# An_lisis_punto_DC.net
KiCad netlist of a schematic drawn in Altium Designer
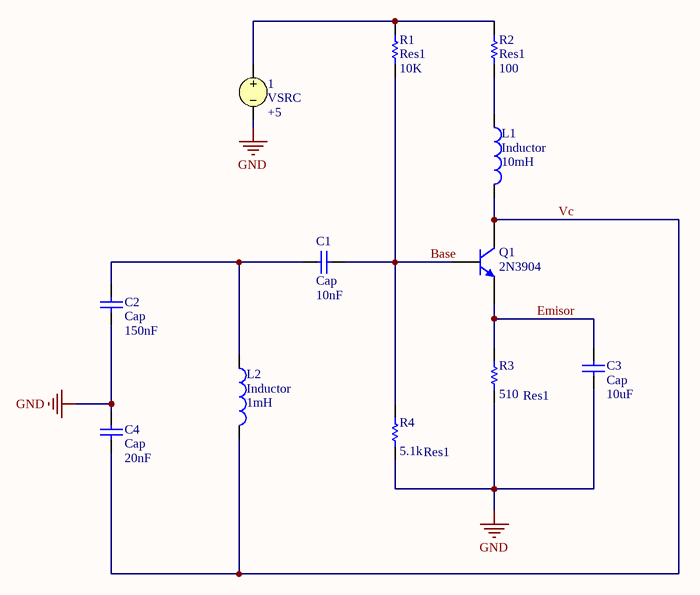
[diagram p0: Análisis_punto_DC.SchDoc]

(export (version "E")
  (design (tool "Eeschema 10.0.6"))
  (components
    (comp (ref "1")
      (value "VSRC")
      (description "Voltage Source")
      (fields (field (name "ALTIUM_VALUE") "+5") (field (name "PUBLISHER") "Altium Limited"))
      (libsource (lib "Simulation Sources") (part "VSRC"))
    )
    (comp (ref "C1")
      (value "Cap")
      (footprint "RAD-0.3")
      (description "Capacitor")
      (fields (field (name "ALTIUM_VALUE") "10nF") (field (name "PUBLISHER") "Altium Limited"))
      (libsource (lib "Miscellaneous Devices") (part "Cap"))
    )
    (comp (ref "C2")
      (value "Cap")
      (footprint "RAD-0.3")
      (description "Capacitor")
      (fields (field (name "ALTIUM_VALUE") "150nF") (field (name "PUBLISHER") "Altium Limited"))
      (libsource (lib "Miscellaneous Devices") (part "Cap"))
    )
    (comp (ref "C3")
      (value "Cap")
      (footprint "RAD-0.3")
      (description "Capacitor")
      (fields (field (name "ALTIUM_VALUE") "10uF") (field (name "PUBLISHER") "Altium Limited"))
      (libsource (lib "Miscellaneous Devices") (part "Cap"))
    )
    (comp (ref "C4")
      (value "Cap")
      (footprint "RAD-0.3")
      (description "Capacitor")
      (fields (field (name "ALTIUM_VALUE") "20nF") (field (name "PUBLISHER") "Altium Limited"))
      (libsource (lib "Miscellaneous Devices") (part "Cap"))
    )
    (comp (ref "L1")
      (value "Inductor")
      (footprint "0402-A")
      (fields (field (name "ALTIUM_VALUE") "10mH") (field (name "PUBLISHER") "Altium Limited"))
      (libsource (lib "Miscellaneous Devices") (part "Inductor"))
    )
    (comp (ref "L2")
      (value "Inductor")
      (footprint "0402-A")
      (fields (field (name "ALTIUM_VALUE") "1mH") (field (name "PUBLISHER") "Altium Limited"))
      (libsource (lib "Miscellaneous Devices") (part "Inductor"))
    )
    (comp (ref "Q1")
      (value "2N3904")
      (footprint "TO-92A")
      (description "NPN General Purpose Amplifier")
      (fields (field (name "PUBLISHER") "Altium Limited"))
      (libsource (lib "Miscellaneous Devices") (part "2N3904"))
    )
    (comp (ref "R1")
      (value "Res1")
      (footprint "AXIAL-0.3")
      (description "Resistor")
      (fields (field (name "ALTIUM_VALUE") "10K") (field (name "PUBLISHER") "Altium Limited"))
      (libsource (lib "Miscellaneous Devices") (part "Res1"))
    )
    (comp (ref "R2")
      (value "Res1")
      (footprint "AXIAL-0.3")
      (description "Resistor")
      (fields (field (name "ALTIUM_VALUE") "100") (field (name "PUBLISHER") "Altium Limited"))
      (libsource (lib "Miscellaneous Devices") (part "Res1"))
    )
    (comp (ref "R3")
      (value "Res1")
      (footprint "AXIAL-0.3")
      (description "Resistor")
      (fields (field (name "ALTIUM_VALUE") "510") (field (name "PUBLISHER") "Altium Limited"))
      (libsource (lib "Miscellaneous Devices") (part "Res1"))
    )
    (comp (ref "R4")
      (value "Res1")
      (footprint "AXIAL-0.3")
      (description "Resistor")
      (fields (field (name "ALTIUM_VALUE") "5.1k") (field (name "PUBLISHER") "Altium Limited"))
      (libsource (lib "Miscellaneous Devices") (part "Res1"))
    )
  )
  (nets
    (net (code "1") (name "/Base") (class "Default")
      (node (ref "C1") (pin "1") (pinfunction "1_1") (pintype "passive"))
      (node (ref "Q1") (pin "2") (pinfunction "B_2") (pintype "passive"))
      (node (ref "R1") (pin "1") (pinfunction "1_1") (pintype "passive"))
      (node (ref "R4") (pin "2") (pinfunction "2_2") (pintype "passive"))
    )
    (net (code "2") (name "/Emisor") (class "Default")
      (node (ref "C3") (pin "2") (pinfunction "2_2") (pintype "passive"))
      (node (ref "Q1") (pin "1") (pinfunction "E_1") (pintype "passive"))
      (node (ref "R3") (pin "2") (pinfunction "2_2") (pintype "passive"))
    )
    (net (code "3") (name "/Vc") (class "Default")
      (node (ref "C4") (pin "1") (pinfunction "1_1") (pintype "passive"))
      (node (ref "L1") (pin "2") (pinfunction "2_2") (pintype "passive"))
      (node (ref "L2") (pin "2") (pinfunction "2_2") (pintype "passive"))
      (node (ref "Q1") (pin "3") (pinfunction "C_3") (pintype "passive"))
    )
    (net (code "4") (name "GND") (class "Default")
      (node (ref "1") (pin "2") (pinfunction "2_2") (pintype "passive"))
      (node (ref "C2") (pin "1") (pinfunction "1_1") (pintype "passive"))
      (node (ref "C3") (pin "1") (pinfunction "1_1") (pintype "passive"))
      (node (ref "C4") (pin "2") (pinfunction "2_2") (pintype "passive"))
      (node (ref "R3") (pin "1") (pinfunction "1_1") (pintype "passive"))
      (node (ref "R4") (pin "1") (pinfunction "1_1") (pintype "passive"))
    )
    (net (code "5") (name "Net-(1-Pad1)") (class "Default")
      (node (ref "1") (pin "1") (pinfunction "1_1") (pintype "passive"))
      (node (ref "R1") (pin "2") (pinfunction "2_2") (pintype "passive"))
      (node (ref "R2") (pin "2") (pinfunction "2_2") (pintype "passive"))
    )
    (net (code "6") (name "Net-(C1-Pad2)") (class "Default")
      (node (ref "C1") (pin "2") (pinfunction "2_2") (pintype "passive"))
      (node (ref "C2") (pin "2") (pinfunction "2_2") (pintype "passive"))
      (node (ref "L2") (pin "1") (pinfunction "1_1") (pintype "passive"))
    )
    (net (code "7") (name "Net-(L1-Pad1)") (class "Default")
      (node (ref "L1") (pin "1") (pinfunction "1_1") (pintype "passive"))
      (node (ref "R2") (pin "1") (pinfunction "1_1") (pintype "passive"))
    )
  )
)
